# rpi-radio.net
KiCad netlist of a schematic drawn in EAGLE
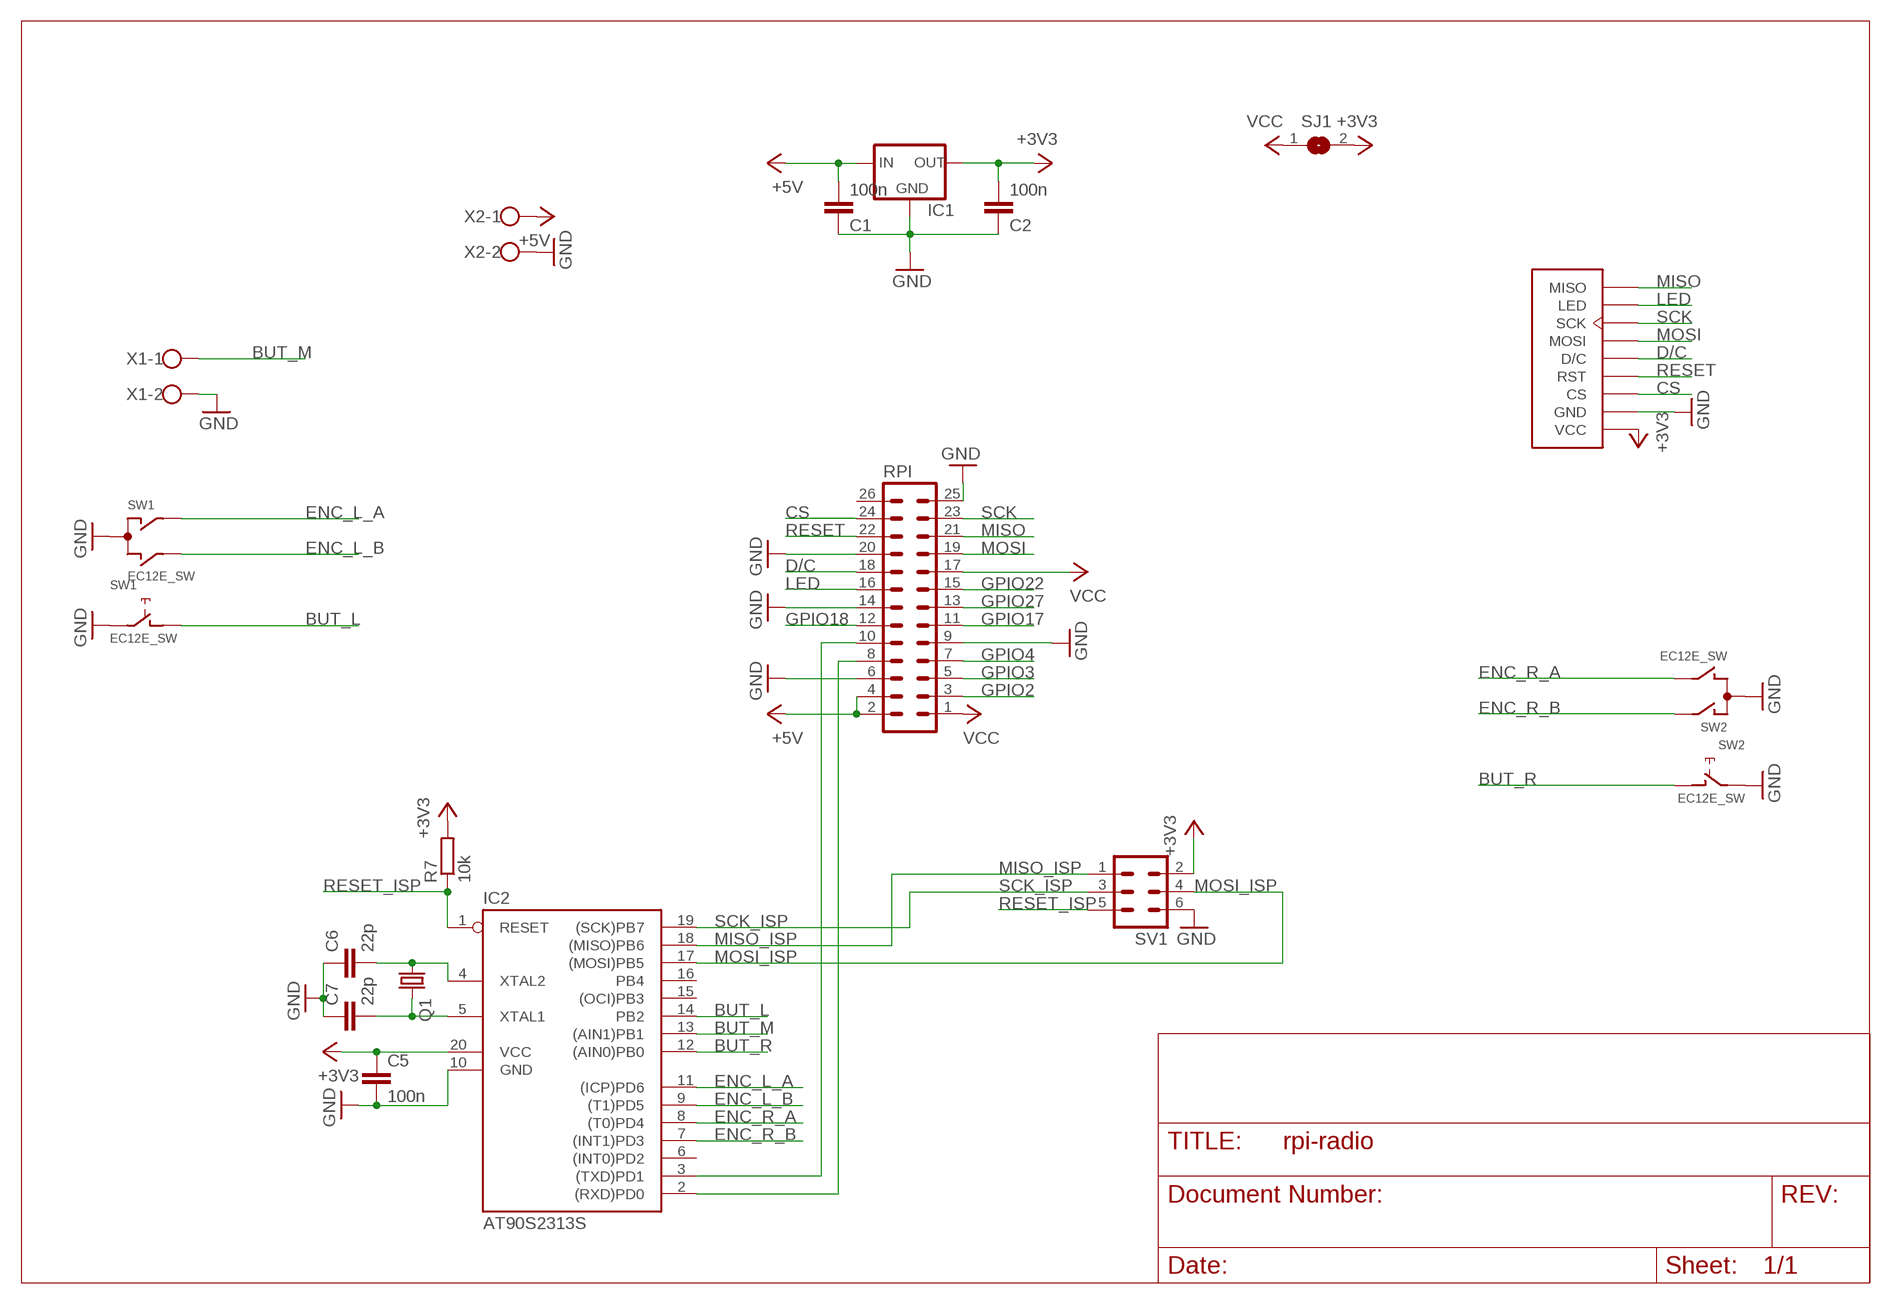
[diagram p0: schematic, sheet 1]

(export (version "E")
  (design (tool "Eeschema 10.0.6"))
  (components
    (comp (ref "C1")
      (value "100n")
      (footprint "eagle-import:C0805")
      (libsource (lib "eagle-import") (part "C-EUC0805"))
    )
    (comp (ref "C2")
      (value "100n")
      (footprint "eagle-import:C0805")
      (libsource (lib "eagle-import") (part "C-EUC0805"))
    )
    (comp (ref "C5")
      (value "100n")
      (footprint "eagle-import:C0805")
      (libsource (lib "eagle-import") (part "C-EUC0805"))
    )
    (comp (ref "C6")
      (value "22p")
      (footprint "eagle-import:C0805")
      (libsource (lib "eagle-import") (part "C-EUC0805"))
    )
    (comp (ref "C7")
      (value "22p")
      (footprint "eagle-import:C0805")
      (libsource (lib "eagle-import") (part "C-EUC0805"))
    )
    (comp (ref "IC1")
      (value "78XXS")
      (footprint "eagle-import:78XXS")
      (libsource (lib "eagle-import") (part "78XXS"))
    )
    (comp (ref "IC2")
      (value "AT90S2313S")
      (footprint "eagle-import:SO20L")
      (libsource (lib "eagle-import") (part "AT90S2313S"))
    )
    (comp (ref "Q1")
      (value "CRYSTALHC49S")
      (footprint "eagle-import:HC49_S")
      (libsource (lib "eagle-import") (part "CRYSTALHC49S"))
    )
    (comp (ref "R7")
      (value "10k")
      (footprint "eagle-import:M0805")
      (libsource (lib "eagle-import") (part "R-EU_M0805"))
    )
    (comp (ref "RPI")
      (value "ML26")
      (footprint "eagle-import:ML26")
      (libsource (lib "eagle-import") (part "ML26"))
    )
    (comp (ref "SJ1") (value "SJ") (footprint "eagle-import:SJ") (libsource (lib "eagle-import") (part "SJ")))
    (comp (ref "SV1")
      (value "ML6")
      (footprint "eagle-import:ML6")
      (libsource (lib "eagle-import") (part "ML6"))
    )
    (comp (ref "SW1")
      (value "EC12E_SW")
      (footprint "eagle-import:ALPS_EC12E_SW")
      (fields (field (name "MPN") "EC12E2424407"))
      (libsource (lib "eagle-import") (part "EC12E_SW"))
    )
    (comp (ref "SW2")
      (value "EC12E_SW")
      (footprint "eagle-import:ALPS_EC12E_SW")
      (fields (field (name "MPN") "EC12E2424407"))
      (libsource (lib "eagle-import") (part "EC12E_SW"))
    )
    (comp (ref "U$4")
      (value "DISPLAY")
      (footprint "eagle-import:DISPLAY")
      (libsource (lib "eagle-import") (part "DISPLAY"))
    )
    (comp (ref "X1")
      (value "W237-102")
      (footprint "eagle-import:W237-102")
      (fields (field (name "MPN") "237-102"))
      (libsource (lib "eagle-import") (part "W237-102"))
    )
    (comp (ref "X2")
      (value "W237-102")
      (footprint "eagle-import:W237-102")
      (fields (field (name "MPN") "237-102"))
      (libsource (lib "eagle-import") (part "W237-102"))
    )
  )
  (nets
    (net (code "1") (name "+3V3") (class "Default")
      (node (ref "C2") (pin "2") (pinfunction "2_2") (pintype "passive"))
      (node (ref "C5") (pin "1") (pinfunction "1_1") (pintype "passive"))
      (node (ref "IC1") (pin "OUT") (pinfunction "OUT_OUT") (pintype "passive"))
      (node (ref "IC2") (pin "20") (pinfunction "VCC_20") (pintype "power_in"))
      (node (ref "R7") (pin "2") (pinfunction "2_2") (pintype "passive"))
      (node (ref "SJ1") (pin "2") (pinfunction "2_2") (pintype "passive"))
      (node (ref "SV1") (pin "2") (pinfunction "2_2") (pintype "passive"))
      (node (ref "U$4") (pin "P$1") (pinfunction "VCC_P$1") (pintype "power_in"))
    )
    (net (code "2") (name "+5V") (class "Default")
      (node (ref "C1") (pin "2") (pinfunction "2_2") (pintype "passive"))
      (node (ref "IC1") (pin "IN") (pinfunction "IN_IN") (pintype "input"))
      (node (ref "RPI") (pin "2") (pinfunction "2_2") (pintype "passive"))
      (node (ref "RPI") (pin "4") (pinfunction "4_4") (pintype "passive"))
      (node (ref "X2") (pin "1") (pinfunction "KL_1") (pintype "passive"))
    )
    (net (code "3") (name "/BUT_L") (class "Default")
      (node (ref "IC2") (pin "14") (pinfunction "PB2_14") (pintype "bidirectional"))
      (node (ref "SW1") (pin "D") (pinfunction "1_D") (pintype "passive"))
    )
    (net (code "4") (name "/BUT_M") (class "Default")
      (node (ref "IC2") (pin "13") (pinfunction "(AIN1)PB1_13") (pintype "bidirectional"))
      (node (ref "X1") (pin "1") (pinfunction "KL_1") (pintype "passive"))
    )
    (net (code "5") (name "/BUT_R") (class "Default")
      (node (ref "IC2") (pin "12") (pinfunction "(AIN0)PB0_12") (pintype "bidirectional"))
      (node (ref "SW2") (pin "D") (pinfunction "1_D") (pintype "passive"))
    )
    (net (code "6") (name "/CS") (class "Default")
      (node (ref "RPI") (pin "24") (pinfunction "24_24") (pintype "passive"))
      (node (ref "U$4") (pin "P$3") (pinfunction "CS_P$3") (pintype "input"))
    )
    (net (code "7") (name "/D{slash}C") (class "Default")
      (node (ref "RPI") (pin "18") (pinfunction "18_18") (pintype "passive"))
      (node (ref "U$4") (pin "P$5") (pinfunction "D/C_P$5") (pintype "bidirectional"))
    )
    (net (code "8") (name "/ENC_L_A") (class "Default")
      (node (ref "IC2") (pin "11") (pinfunction "(ICP)PD6_11") (pintype "bidirectional"))
      (node (ref "SW1") (pin "A") (pinfunction "A_A") (pintype "passive"))
    )
    (net (code "9") (name "/ENC_L_B") (class "Default")
      (node (ref "IC2") (pin "9") (pinfunction "(T1)PD5_9") (pintype "bidirectional"))
      (node (ref "SW1") (pin "B") (pinfunction "B_B") (pintype "passive"))
    )
    (net (code "10") (name "/ENC_R_A") (class "Default")
      (node (ref "IC2") (pin "8") (pinfunction "(T0)PD4_8") (pintype "bidirectional"))
      (node (ref "SW2") (pin "B") (pinfunction "B_B") (pintype "passive"))
    )
    (net (code "11") (name "/ENC_R_B") (class "Default")
      (node (ref "IC2") (pin "7") (pinfunction "(INT1)PD3_7") (pintype "bidirectional"))
      (node (ref "SW2") (pin "A") (pinfunction "A_A") (pintype "passive"))
    )
    (net (code "12") (name "/GPIO2") (class "Default")
      (node (ref "RPI") (pin "3") (pinfunction "3_3") (pintype "passive"))
    )
    (net (code "13") (name "/GPIO3") (class "Default")
      (node (ref "RPI") (pin "5") (pinfunction "5_5") (pintype "passive"))
    )
    (net (code "14") (name "/GPIO4") (class "Default")
      (node (ref "RPI") (pin "7") (pinfunction "7_7") (pintype "passive"))
    )
    (net (code "15") (name "/GPIO17") (class "Default")
      (node (ref "RPI") (pin "11") (pinfunction "11_11") (pintype "passive"))
    )
    (net (code "16") (name "/GPIO18") (class "Default")
      (node (ref "RPI") (pin "12") (pinfunction "12_12") (pintype "passive"))
    )
    (net (code "17") (name "/GPIO22") (class "Default")
      (node (ref "RPI") (pin "15") (pinfunction "15_15") (pintype "passive"))
    )
    (net (code "18") (name "/GPIO27") (class "Default")
      (node (ref "RPI") (pin "13") (pinfunction "13_13") (pintype "passive"))
    )
    (net (code "19") (name "/LED") (class "Default")
      (node (ref "RPI") (pin "16") (pinfunction "16_16") (pintype "passive"))
      (node (ref "U$4") (pin "P$8") (pinfunction "LED_P$8") (pintype "power_in"))
    )
    (net (code "20") (name "/MISO") (class "Default")
      (node (ref "RPI") (pin "21") (pinfunction "21_21") (pintype "passive"))
      (node (ref "U$4") (pin "P$9") (pinfunction "MISO_P$9") (pintype "output"))
    )
    (net (code "21") (name "/MISO_ISP") (class "Default")
      (node (ref "IC2") (pin "18") (pinfunction "(MISO)PB6_18") (pintype "bidirectional"))
      (node (ref "SV1") (pin "1") (pinfunction "1_1") (pintype "passive"))
    )
    (net (code "22") (name "/MOSI") (class "Default")
      (node (ref "RPI") (pin "19") (pinfunction "19_19") (pintype "passive"))
      (node (ref "U$4") (pin "P$6") (pinfunction "MOSI_P$6") (pintype "input"))
    )
    (net (code "23") (name "/MOSI_ISP") (class "Default")
      (node (ref "IC2") (pin "17") (pinfunction "(MOSI)PB5_17") (pintype "bidirectional"))
      (node (ref "SV1") (pin "4") (pinfunction "4_4") (pintype "passive"))
    )
    (net (code "24") (name "/RESET") (class "Default")
      (node (ref "RPI") (pin "22") (pinfunction "22_22") (pintype "passive"))
      (node (ref "U$4") (pin "P$4") (pinfunction "RST_P$4") (pintype "input"))
    )
    (net (code "25") (name "/RESET_ISP") (class "Default")
      (node (ref "IC2") (pin "1") (pinfunction "RESET_1") (pintype "bidirectional"))
      (node (ref "R7") (pin "1") (pinfunction "1_1") (pintype "passive"))
      (node (ref "SV1") (pin "5") (pinfunction "5_5") (pintype "passive"))
    )
    (net (code "26") (name "/SCK") (class "Default")
      (node (ref "RPI") (pin "23") (pinfunction "23_23") (pintype "passive"))
      (node (ref "U$4") (pin "P$7") (pinfunction "SCK_P$7") (pintype "input"))
    )
    (net (code "27") (name "/SCK_ISP") (class "Default")
      (node (ref "IC2") (pin "19") (pinfunction "(SCK)PB7_19") (pintype "bidirectional"))
      (node (ref "SV1") (pin "3") (pinfunction "3_3") (pintype "passive"))
    )
    (net (code "28") (name "GND") (class "Default")
      (node (ref "C1") (pin "1") (pinfunction "1_1") (pintype "passive"))
      (node (ref "C2") (pin "1") (pinfunction "1_1") (pintype "passive"))
      (node (ref "C5") (pin "2") (pinfunction "2_2") (pintype "passive"))
      (node (ref "C6") (pin "1") (pinfunction "1_1") (pintype "passive"))
      (node (ref "C7") (pin "1") (pinfunction "1_1") (pintype "passive"))
      (node (ref "IC1") (pin "GND") (pinfunction "GND_GND") (pintype "input"))
      (node (ref "IC2") (pin "10") (pinfunction "GND_10") (pintype "power_in"))
      (node (ref "RPI") (pin "14") (pinfunction "14_14") (pintype "passive"))
      (node (ref "RPI") (pin "20") (pinfunction "20_20") (pintype "passive"))
      (node (ref "RPI") (pin "25") (pinfunction "25_25") (pintype "passive"))
      (node (ref "RPI") (pin "6") (pinfunction "6_6") (pintype "passive"))
      (node (ref "RPI") (pin "9") (pinfunction "9_9") (pintype "passive"))
      (node (ref "SV1") (pin "6") (pinfunction "6_6") (pintype "passive"))
      (node (ref "SW1") (pin "C") (pinfunction "C_C") (pintype "passive"))
      (node (ref "SW1") (pin "E") (pinfunction "2_E") (pintype "passive"))
      (node (ref "SW2") (pin "C") (pinfunction "C_C") (pintype "passive"))
      (node (ref "SW2") (pin "E") (pinfunction "2_E") (pintype "passive"))
      (node (ref "U$4") (pin "P$2") (pinfunction "GND_P$2") (pintype "power_in"))
      (node (ref "X1") (pin "2") (pinfunction "KL_2") (pintype "passive"))
      (node (ref "X2") (pin "2") (pinfunction "KL_2") (pintype "passive"))
    )
    (net (code "29") (name "Net-(IC2-(RXD)PD0)") (class "Default")
      (node (ref "IC2") (pin "2") (pinfunction "(RXD)PD0_2") (pintype "bidirectional"))
      (node (ref "RPI") (pin "8") (pinfunction "8_8") (pintype "passive"))
    )
    (net (code "30") (name "Net-(IC2-(TXD)PD1)") (class "Default")
      (node (ref "IC2") (pin "3") (pinfunction "(TXD)PD1_3") (pintype "bidirectional"))
      (node (ref "RPI") (pin "10") (pinfunction "10_10") (pintype "passive"))
    )
    (net (code "31") (name "Net-(IC2-XTAL1)") (class "Default")
      (node (ref "C7") (pin "2") (pinfunction "2_2") (pintype "passive"))
      (node (ref "IC2") (pin "5") (pinfunction "XTAL1_5") (pintype "bidirectional"))
      (node (ref "Q1") (pin "2") (pinfunction "2_2") (pintype "passive"))
    )
    (net (code "32") (name "Net-(IC2-XTAL2)") (class "Default")
      (node (ref "C6") (pin "2") (pinfunction "2_2") (pintype "passive"))
      (node (ref "IC2") (pin "4") (pinfunction "XTAL2_4") (pintype "bidirectional"))
      (node (ref "Q1") (pin "1") (pinfunction "1_1") (pintype "passive"))
    )
    (net (code "33") (name "VCC") (class "Default")
      (node (ref "RPI") (pin "1") (pinfunction "1_1") (pintype "passive"))
      (node (ref "RPI") (pin "17") (pinfunction "17_17") (pintype "passive"))
      (node (ref "SJ1") (pin "1") (pinfunction "1_1") (pintype "passive"))
    )
    (net (code "34") (name "unconnected-(IC2-(INT0)PD2-Pad6)") (class "Default")
      (node (ref "IC2") (pin "6") (pinfunction "(INT0)PD2_6") (pintype "bidirectional"))
    )
    (net (code "35") (name "unconnected-(IC2-(OCI)PB3-Pad15)") (class "Default")
      (node (ref "IC2") (pin "15") (pinfunction "(OCI)PB3_15") (pintype "bidirectional"))
    )
    (net (code "36") (name "unconnected-(IC2-PB4-Pad16)") (class "Default")
      (node (ref "IC2") (pin "16") (pinfunction "PB4_16") (pintype "bidirectional"))
    )
    (net (code "37") (name "unconnected-(RPI-Pad26)") (class "Default")
      (node (ref "RPI") (pin "26") (pinfunction "26_26") (pintype "passive"))
    )
  )
)
